# dual_encoder_i2c_revB.net
KiCad netlist of a schematic drawn in EAGLE
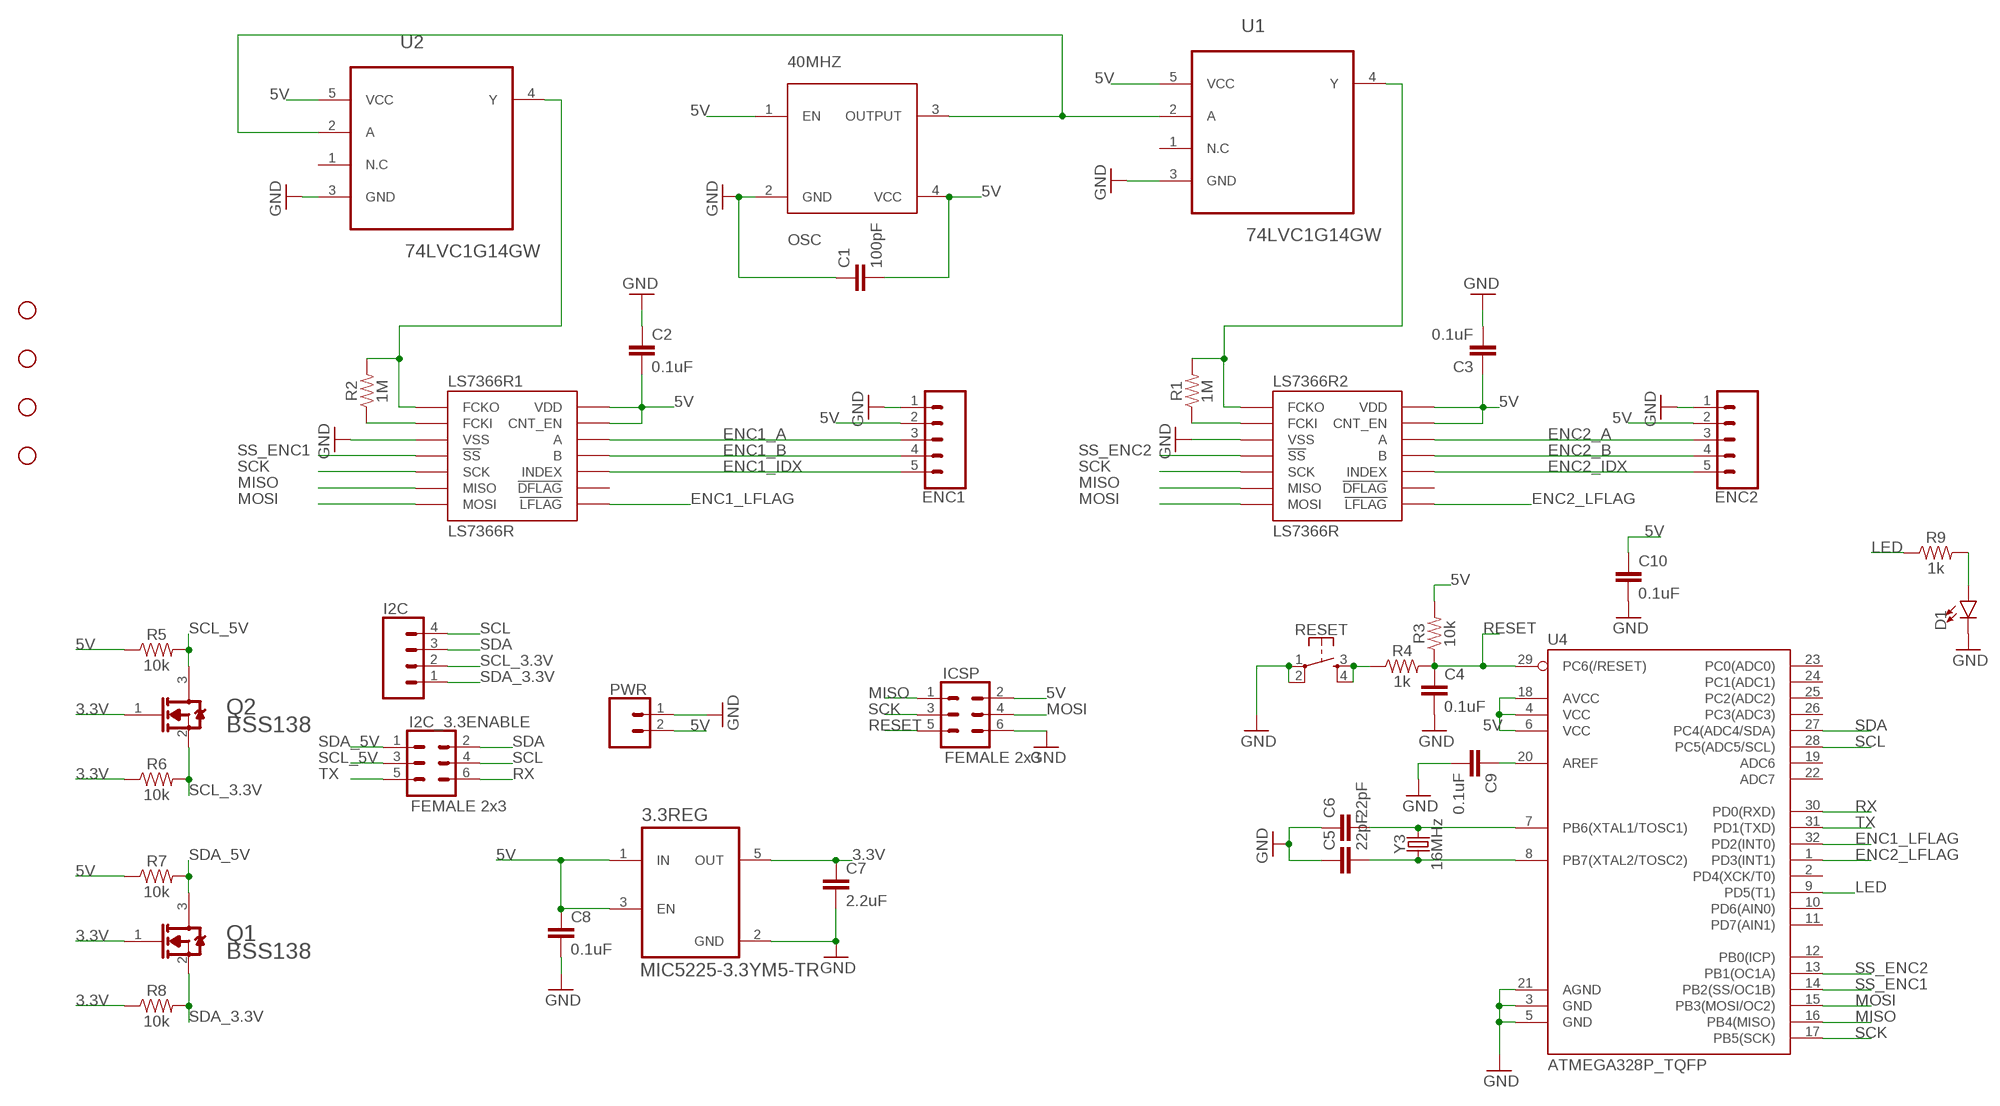
[diagram p0: schematic, sheet 1]

(export (version "E")
  (design (tool "Eeschema 10.0.6"))
  (components
    (comp (ref "3.3REG")
      (value "MIC5225-3.3YM5-TR")
      (footprint "eagle-import:SOT95P280X145-5N")
      (fields (field (name "MF") "Microchip"))
      (libsource (lib "eagle-import") (part "MIC5225-3.3YM5-TR"))
    )
    (comp (ref "40MHZ")
      (value "OSC")
      (footprint "eagle-import:CB3OSCILLATOR")
      (libsource (lib "eagle-import") (part "OSC"))
    )
    (comp (ref "C1")
      (value "100pF")
      (footprint "eagle-import:0603")
      (libsource (lib "eagle-import") (part "100PF-0603-50V-5%"))
    )
    (comp (ref "C2")
      (value "0.1uF")
      (footprint "eagle-import:0603")
      (libsource (lib "eagle-import") (part "0.1UF-0603-25V-5%"))
    )
    (comp (ref "C3")
      (value "0.1uF")
      (footprint "eagle-import:0603")
      (libsource (lib "eagle-import") (part "0.1UF-0603-25V-5%"))
    )
    (comp (ref "C4")
      (value "0.1uF")
      (footprint "eagle-import:0603")
      (libsource (lib "eagle-import") (part "0.1UF-0603-25V-5%"))
    )
    (comp (ref "C5")
      (value "22pF")
      (footprint "eagle-import:0603")
      (libsource (lib "eagle-import") (part "22PF-0603-50V-5%"))
    )
    (comp (ref "C6")
      (value "22pF")
      (footprint "eagle-import:0603")
      (libsource (lib "eagle-import") (part "22PF-0603-50V-5%"))
    )
    (comp (ref "C7")
      (value "2.2uF")
      (footprint "eagle-import:0603")
      (libsource (lib "eagle-import") (part "2.2UF-0603-10V-20%"))
    )
    (comp (ref "C8")
      (value "0.1uF")
      (footprint "eagle-import:0603")
      (libsource (lib "eagle-import") (part "0.1UF-0603-25V-5%"))
    )
    (comp (ref "C9")
      (value "0.1uF")
      (footprint "eagle-import:0603")
      (libsource (lib "eagle-import") (part "0.1UF-0603-25V-5%"))
    )
    (comp (ref "C10")
      (value "0.1uF")
      (footprint "eagle-import:0603")
      (libsource (lib "eagle-import") (part "0.1UF-0603-25V-5%"))
    )
    (comp (ref "D1")
      (value "LED0603")
      (footprint "eagle-import:LED-0603")
      (libsource (lib "eagle-import") (part "LED0603"))
    )
    (comp (ref "ENC1")
      (value "CONN_05")
      (footprint "eagle-import:1X05")
      (libsource (lib "eagle-import") (part "CONN_05"))
    )
    (comp (ref "ENC2")
      (value "CONN_05")
      (footprint "eagle-import:1X05")
      (libsource (lib "eagle-import") (part "CONN_05"))
    )
    (comp (ref "H1")
      (value "STAND-OFF")
      (footprint "eagle-import:STAND-OFF")
      (libsource (lib "eagle-import") (part "STAND-OFF"))
    )
    (comp (ref "H2")
      (value "STAND-OFF")
      (footprint "eagle-import:STAND-OFF")
      (libsource (lib "eagle-import") (part "STAND-OFF"))
    )
    (comp (ref "H3")
      (value "STAND-OFF")
      (footprint "eagle-import:STAND-OFF")
      (libsource (lib "eagle-import") (part "STAND-OFF"))
    )
    (comp (ref "H4")
      (value "STAND-OFF")
      (footprint "eagle-import:STAND-OFF")
      (libsource (lib "eagle-import") (part "STAND-OFF"))
    )
    (comp (ref "I2C")
      (value "CONN_04")
      (footprint "eagle-import:1X04")
      (libsource (lib "eagle-import") (part "CONN_04"))
    )
    (comp (ref "I2C_3.3ENABLE")
      (value "FEMALE 2x3")
      (footprint "eagle-import:2X3")
      (libsource (lib "eagle-import") (part "CONN_03X2FEMALE"))
    )
    (comp (ref "ICSP")
      (value "FEMALE 2x3")
      (footprint "eagle-import:2X3")
      (libsource (lib "eagle-import") (part "CONN_03X2FEMALE"))
    )
    (comp (ref "LS7366R1")
      (value "LS7366R")
      (footprint "eagle-import:SOIC14")
      (fields (field (name "MF") "LSI"))
      (libsource (lib "eagle-import") (part "LS7366R"))
    )
    (comp (ref "LS7366R2")
      (value "LS7366R")
      (footprint "eagle-import:SOIC14")
      (fields (field (name "MF") "LSI"))
      (libsource (lib "eagle-import") (part "LS7366R"))
    )
    (comp (ref "PWR")
      (value "CONN_02-JST-2MM-SMT")
      (footprint "eagle-import:JST-2-SMD")
      (libsource (lib "eagle-import") (part "CONN_02-JST-2MM-SMT"))
    )
    (comp (ref "Q1")
      (value "ON_SEMI_BSS138ON_SEMI_BSS138_0_0")
      (footprint "eagle-import:ON_SEMI_BSS138_0")
      (fields
        (field (name "DIGIKEY_PART_NUMBER") "BSS138CT-ND")
        (field (name "MF") "ON Semi")
        (field (name "MOUSER_PART_NUMBER") "512-BSS138")
      )
      (libsource (lib "eagle-import") (part "ON_SEMI_BSS138ON_SEMI_BSS138_0_0"))
    )
    (comp (ref "Q2")
      (value "ON_SEMI_BSS138ON_SEMI_BSS138_0_0")
      (footprint "eagle-import:ON_SEMI_BSS138_0")
      (fields
        (field (name "DIGIKEY_PART_NUMBER") "BSS138CT-ND")
        (field (name "MF") "ON Semi")
        (field (name "MOUSER_PART_NUMBER") "512-BSS138")
      )
      (libsource (lib "eagle-import") (part "ON_SEMI_BSS138ON_SEMI_BSS138_0_0"))
    )
    (comp (ref "R1")
      (value "1M")
      (footprint "eagle-import:0603")
      (libsource (lib "eagle-import") (part "1MOHM-0603-1/4W-5%"))
    )
    (comp (ref "R2")
      (value "1M")
      (footprint "eagle-import:0603")
      (libsource (lib "eagle-import") (part "1MOHM-0603-1/4W-5%"))
    )
    (comp (ref "R3")
      (value "10k")
      (footprint "eagle-import:0603")
      (libsource (lib "eagle-import") (part "10KOHM-0603-1/10W-1%"))
    )
    (comp (ref "R4")
      (value "1k")
      (footprint "eagle-import:0603")
      (libsource (lib "eagle-import") (part "1KOHM-0603-1/10W-1%"))
    )
    (comp (ref "R5")
      (value "10k")
      (footprint "eagle-import:0603")
      (libsource (lib "eagle-import") (part "10KOHM-0603-1/10W-1%"))
    )
    (comp (ref "R6")
      (value "10k")
      (footprint "eagle-import:0603")
      (libsource (lib "eagle-import") (part "10KOHM-0603-1/10W-1%"))
    )
    (comp (ref "R7")
      (value "10k")
      (footprint "eagle-import:0603")
      (libsource (lib "eagle-import") (part "10KOHM-0603-1/10W-1%"))
    )
    (comp (ref "R8")
      (value "10k")
      (footprint "eagle-import:0603")
      (libsource (lib "eagle-import") (part "10KOHM-0603-1/10W-1%"))
    )
    (comp (ref "R9")
      (value "1k")
      (footprint "eagle-import:0603")
      (libsource (lib "eagle-import") (part "1KOHM-0603-1/10W-1%"))
    )
    (comp (ref "RESET")
      (value "MOMENTARY-SWITCH-SPST-2-SMD-5.2MM")
      (footprint "eagle-import:TACTILE_SWITCH_SMD_5.2MM")
      (libsource (lib "eagle-import") (part "MOMENTARY-SWITCH-SPST-2-SMD-5.2MM"))
    )
    (comp (ref "U1")
      (value "74LVC1G14GW")
      (footprint "eagle-import:SOT65P210X110-5N")
      (fields (field (name "MF") "NXP Semiconductors"))
      (libsource (lib "eagle-import") (part "74LVC1G14GW"))
    )
    (comp (ref "U2")
      (value "74LVC1G14GW")
      (footprint "eagle-import:SOT65P210X110-5N")
      (fields (field (name "MF") "NXP Semiconductors"))
      (libsource (lib "eagle-import") (part "74LVC1G14GW"))
    )
    (comp (ref "U4")
      (value "ATMEGA328P_TQFP")
      (footprint "eagle-import:TQFP32-08")
      (libsource (lib "eagle-import") (part "ATMEGA328P_TQFP"))
    )
    (comp (ref "Y3")
      (value "16MHz")
      (footprint "eagle-import:CRYSTAL-SMD-5X3.2-4PAD")
      (libsource (lib "eagle-import") (part "CRYSTAL-16MHZSMD-5X3.2"))
    )
  )
  (nets
    (net (code "1") (name "/3.3V") (class "Default")
      (node (ref "3.3REG") (pin "5") (pinfunction "OUT_5") (pintype "output"))
      (node (ref "C7") (pin "1") (pinfunction "1_1") (pintype "passive"))
      (node (ref "Q1") (pin "1") (pinfunction "G_1") (pintype "bidirectional"))
      (node (ref "Q2") (pin "1") (pinfunction "G_1") (pintype "bidirectional"))
      (node (ref "R6") (pin "1") (pinfunction "1_1") (pintype "passive"))
      (node (ref "R8") (pin "1") (pinfunction "1_1") (pintype "passive"))
    )
    (net (code "2") (name "/5V") (class "Default")
      (node (ref "3.3REG") (pin "1") (pinfunction "IN_1") (pintype "input"))
      (node (ref "3.3REG") (pin "3") (pinfunction "EN_3") (pintype "input"))
      (node (ref "40MHZ") (pin "1") (pinfunction "EN_1") (pintype "input"))
      (node (ref "40MHZ") (pin "4") (pinfunction "VCC_4") (pintype "input"))
      (node (ref "C1") (pin "2") (pinfunction "2_2") (pintype "passive"))
      (node (ref "C10") (pin "1") (pinfunction "1_1") (pintype "passive"))
      (node (ref "C2") (pin "2") (pinfunction "2_2") (pintype "passive"))
      (node (ref "C3") (pin "1") (pinfunction "1_1") (pintype "passive"))
      (node (ref "C8") (pin "1") (pinfunction "1_1") (pintype "passive"))
      (node (ref "ENC1") (pin "2") (pinfunction "2_2") (pintype "passive"))
      (node (ref "ENC2") (pin "2") (pinfunction "2_2") (pintype "passive"))
      (node (ref "ICSP") (pin "2") (pinfunction "2_2") (pintype "bidirectional"))
      (node (ref "LS7366R1") (pin "13") (pinfunction "CNT_EN_13") (pintype "bidirectional"))
      (node (ref "LS7366R1") (pin "14") (pinfunction "VDD_14") (pintype "bidirectional"))
      (node (ref "LS7366R2") (pin "13") (pinfunction "CNT_EN_13") (pintype "bidirectional"))
      (node (ref "LS7366R2") (pin "14") (pinfunction "VDD_14") (pintype "bidirectional"))
      (node (ref "PWR") (pin "2") (pinfunction "1_2") (pintype "passive"))
      (node (ref "R3") (pin "2") (pinfunction "2_2") (pintype "passive"))
      (node (ref "R5") (pin "1") (pinfunction "1_1") (pintype "passive"))
      (node (ref "R7") (pin "1") (pinfunction "1_1") (pintype "passive"))
      (node (ref "U1") (pin "5") (pinfunction "VCC_5") (pintype "power_in"))
      (node (ref "U2") (pin "5") (pinfunction "VCC_5") (pintype "power_in"))
      (node (ref "U4") (pin "18") (pinfunction "AVCC_18") (pintype "bidirectional"))
      (node (ref "U4") (pin "4") (pinfunction "VCC_4") (pintype "bidirectional"))
      (node (ref "U4") (pin "6") (pinfunction "VCC_6") (pintype "bidirectional"))
    )
    (net (code "3") (name "/ENC1_A") (class "Default")
      (node (ref "ENC1") (pin "3") (pinfunction "3_3") (pintype "passive"))
      (node (ref "LS7366R1") (pin "12") (pinfunction "A_12") (pintype "bidirectional"))
    )
    (net (code "4") (name "/ENC1_B") (class "Default")
      (node (ref "ENC1") (pin "4") (pinfunction "4_4") (pintype "passive"))
      (node (ref "LS7366R1") (pin "11") (pinfunction "B_11") (pintype "bidirectional"))
    )
    (net (code "5") (name "/ENC1_IDX") (class "Default")
      (node (ref "ENC1") (pin "5") (pinfunction "5_5") (pintype "passive"))
      (node (ref "LS7366R1") (pin "10") (pinfunction "INDEX_10") (pintype "bidirectional"))
    )
    (net (code "6") (name "/ENC1_LFLAG") (class "Default")
      (node (ref "LS7366R1") (pin "8") (pinfunction "~{LFLAG}_8") (pintype "bidirectional"))
      (node (ref "U4") (pin "32") (pinfunction "PD2(INT0)_32") (pintype "bidirectional"))
    )
    (net (code "7") (name "/ENC2_A") (class "Default")
      (node (ref "ENC2") (pin "3") (pinfunction "3_3") (pintype "passive"))
      (node (ref "LS7366R2") (pin "12") (pinfunction "A_12") (pintype "bidirectional"))
    )
    (net (code "8") (name "/ENC2_B") (class "Default")
      (node (ref "ENC2") (pin "4") (pinfunction "4_4") (pintype "passive"))
      (node (ref "LS7366R2") (pin "11") (pinfunction "B_11") (pintype "bidirectional"))
    )
    (net (code "9") (name "/ENC2_IDX") (class "Default")
      (node (ref "ENC2") (pin "5") (pinfunction "5_5") (pintype "passive"))
      (node (ref "LS7366R2") (pin "10") (pinfunction "INDEX_10") (pintype "bidirectional"))
    )
    (net (code "10") (name "/ENC2_LFLAG") (class "Default")
      (node (ref "LS7366R2") (pin "8") (pinfunction "~{LFLAG}_8") (pintype "bidirectional"))
      (node (ref "U4") (pin "1") (pinfunction "PD3(INT1)_1") (pintype "bidirectional"))
    )
    (net (code "11") (name "/LED") (class "Default")
      (node (ref "R9") (pin "1") (pinfunction "1_1") (pintype "passive"))
      (node (ref "U4") (pin "9") (pinfunction "PD5(T1)_9") (pintype "bidirectional"))
    )
    (net (code "12") (name "/MISO") (class "Default")
      (node (ref "ICSP") (pin "1") (pinfunction "1_1") (pintype "bidirectional"))
      (node (ref "LS7366R1") (pin "6") (pinfunction "MISO_6") (pintype "bidirectional"))
      (node (ref "LS7366R2") (pin "6") (pinfunction "MISO_6") (pintype "bidirectional"))
      (node (ref "U4") (pin "16") (pinfunction "PB4(MISO)_16") (pintype "bidirectional"))
    )
    (net (code "13") (name "/MOSI") (class "Default")
      (node (ref "ICSP") (pin "4") (pinfunction "4_4") (pintype "bidirectional"))
      (node (ref "LS7366R1") (pin "7") (pinfunction "MOSI_7") (pintype "bidirectional"))
      (node (ref "LS7366R2") (pin "7") (pinfunction "MOSI_7") (pintype "bidirectional"))
      (node (ref "U4") (pin "15") (pinfunction "PB3(MOSI/OC2)_15") (pintype "bidirectional"))
    )
    (net (code "14") (name "/RESET") (class "Default")
      (node (ref "C4") (pin "1") (pinfunction "1_1") (pintype "passive"))
      (node (ref "ICSP") (pin "5") (pinfunction "5_5") (pintype "bidirectional"))
      (node (ref "R3") (pin "1") (pinfunction "1_1") (pintype "passive"))
      (node (ref "R4") (pin "2") (pinfunction "2_2") (pintype "passive"))
      (node (ref "U4") (pin "29") (pinfunction "PC6(/RESET)_29") (pintype "bidirectional"))
    )
    (net (code "15") (name "/RX") (class "Default")
      (node (ref "I2C_3.3ENABLE") (pin "6") (pinfunction "6_6") (pintype "bidirectional"))
      (node (ref "U4") (pin "30") (pinfunction "PD0(RXD)_30") (pintype "bidirectional"))
    )
    (net (code "16") (name "/SCK") (class "Default")
      (node (ref "ICSP") (pin "3") (pinfunction "3_3") (pintype "bidirectional"))
      (node (ref "LS7366R1") (pin "5") (pinfunction "SCK_5") (pintype "bidirectional"))
      (node (ref "LS7366R2") (pin "5") (pinfunction "SCK_5") (pintype "bidirectional"))
      (node (ref "U4") (pin "17") (pinfunction "PB5(SCK)_17") (pintype "bidirectional"))
    )
    (net (code "17") (name "/SCL") (class "Default")
      (node (ref "I2C") (pin "4") (pinfunction "4_4") (pintype "passive"))
      (node (ref "I2C_3.3ENABLE") (pin "4") (pinfunction "4_4") (pintype "bidirectional"))
      (node (ref "U4") (pin "28") (pinfunction "PC5(ADC5/SCL)_28") (pintype "bidirectional"))
    )
    (net (code "18") (name "/SCL_3.3V") (class "Default")
      (node (ref "I2C") (pin "2") (pinfunction "2_2") (pintype "passive"))
      (node (ref "Q2") (pin "2") (pinfunction "S_2") (pintype "bidirectional"))
      (node (ref "R6") (pin "2") (pinfunction "2_2") (pintype "passive"))
    )
    (net (code "19") (name "/SCL_5V") (class "Default")
      (node (ref "I2C_3.3ENABLE") (pin "3") (pinfunction "3_3") (pintype "bidirectional"))
      (node (ref "Q2") (pin "3") (pinfunction "D_3") (pintype "bidirectional"))
      (node (ref "R5") (pin "2") (pinfunction "2_2") (pintype "passive"))
    )
    (net (code "20") (name "/SDA") (class "Default")
      (node (ref "I2C") (pin "3") (pinfunction "3_3") (pintype "passive"))
      (node (ref "I2C_3.3ENABLE") (pin "2") (pinfunction "2_2") (pintype "bidirectional"))
      (node (ref "U4") (pin "27") (pinfunction "PC4(ADC4/SDA)_27") (pintype "bidirectional"))
    )
    (net (code "21") (name "/SDA_3.3V") (class "Default")
      (node (ref "I2C") (pin "1") (pinfunction "1_1") (pintype "passive"))
      (node (ref "Q1") (pin "2") (pinfunction "S_2") (pintype "bidirectional"))
      (node (ref "R8") (pin "2") (pinfunction "2_2") (pintype "passive"))
    )
    (net (code "22") (name "/SDA_5V") (class "Default")
      (node (ref "I2C_3.3ENABLE") (pin "1") (pinfunction "1_1") (pintype "bidirectional"))
      (node (ref "Q1") (pin "3") (pinfunction "D_3") (pintype "bidirectional"))
      (node (ref "R7") (pin "2") (pinfunction "2_2") (pintype "passive"))
    )
    (net (code "23") (name "/SS_ENC1") (class "Default")
      (node (ref "LS7366R1") (pin "4") (pinfunction "~{SS}_4") (pintype "bidirectional"))
      (node (ref "U4") (pin "14") (pinfunction "PB2(SS/OC1B)_14") (pintype "bidirectional"))
    )
    (net (code "24") (name "/SS_ENC2") (class "Default")
      (node (ref "LS7366R2") (pin "4") (pinfunction "~{SS}_4") (pintype "bidirectional"))
      (node (ref "U4") (pin "13") (pinfunction "PB1(OC1A)_13") (pintype "bidirectional"))
    )
    (net (code "25") (name "/TX") (class "Default")
      (node (ref "I2C_3.3ENABLE") (pin "5") (pinfunction "5_5") (pintype "bidirectional"))
      (node (ref "U4") (pin "31") (pinfunction "PD1(TXD)_31") (pintype "bidirectional"))
    )
    (net (code "26") (name "GND") (class "Default")
      (node (ref "3.3REG") (pin "2") (pinfunction "GND_2") (pintype "power_in"))
      (node (ref "40MHZ") (pin "2") (pinfunction "GND_2") (pintype "input"))
      (node (ref "C1") (pin "1") (pinfunction "1_1") (pintype "passive"))
      (node (ref "C10") (pin "2") (pinfunction "2_2") (pintype "passive"))
      (node (ref "C2") (pin "1") (pinfunction "1_1") (pintype "passive"))
      (node (ref "C3") (pin "2") (pinfunction "2_2") (pintype "passive"))
      (node (ref "C4") (pin "2") (pinfunction "2_2") (pintype "passive"))
      (node (ref "C5") (pin "1") (pinfunction "1_1") (pintype "passive"))
      (node (ref "C6") (pin "1") (pinfunction "1_1") (pintype "passive"))
      (node (ref "C7") (pin "2") (pinfunction "2_2") (pintype "passive"))
      (node (ref "C8") (pin "2") (pinfunction "2_2") (pintype "passive"))
      (node (ref "C9") (pin "2") (pinfunction "2_2") (pintype "passive"))
      (node (ref "D1") (pin "C") (pinfunction "C_C") (pintype "passive"))
      (node (ref "ENC1") (pin "1") (pinfunction "1_1") (pintype "passive"))
      (node (ref "ENC2") (pin "1") (pinfunction "1_1") (pintype "passive"))
      (node (ref "ICSP") (pin "6") (pinfunction "6_6") (pintype "bidirectional"))
      (node (ref "LS7366R1") (pin "3") (pinfunction "VSS_3") (pintype "bidirectional"))
      (node (ref "LS7366R2") (pin "3") (pinfunction "VSS_3") (pintype "bidirectional"))
      (node (ref "PWR") (pin "1") (pinfunction "2_1") (pintype "passive"))
      (node (ref "RESET") (pin "1") (pinfunction "1_1") (pintype "passive"))
      (node (ref "RESET") (pin "2") (pinfunction "2_2") (pintype "passive"))
      (node (ref "U1") (pin "3") (pinfunction "GND_3") (pintype "passive"))
      (node (ref "U2") (pin "3") (pinfunction "GND_3") (pintype "passive"))
      (node (ref "U4") (pin "21") (pinfunction "AGND_21") (pintype "bidirectional"))
      (node (ref "U4") (pin "3") (pinfunction "GND_3") (pintype "bidirectional"))
      (node (ref "U4") (pin "5") (pinfunction "GND_5") (pintype "bidirectional"))
    )
    (net (code "27") (name "Net-(40MHZ-OUTPUT)") (class "Default")
      (node (ref "40MHZ") (pin "3") (pinfunction "OUTPUT_3") (pintype "output"))
      (node (ref "U1") (pin "2") (pinfunction "A_2") (pintype "input"))
      (node (ref "U2") (pin "2") (pinfunction "A_2") (pintype "input"))
    )
    (net (code "28") (name "Net-(D1-PadA)") (class "Default")
      (node (ref "D1") (pin "A") (pinfunction "A_A") (pintype "passive"))
      (node (ref "R9") (pin "2") (pinfunction "2_2") (pintype "passive"))
    )
    (net (code "29") (name "Net-(LS7366R1-FCKI)") (class "Default")
      (node (ref "LS7366R1") (pin "2") (pinfunction "FCKI_2") (pintype "bidirectional"))
      (node (ref "R2") (pin "1") (pinfunction "1_1") (pintype "passive"))
    )
    (net (code "30") (name "Net-(LS7366R1-FCKO)") (class "Default")
      (node (ref "LS7366R1") (pin "1") (pinfunction "FCKO_1") (pintype "bidirectional"))
      (node (ref "R2") (pin "2") (pinfunction "2_2") (pintype "passive"))
      (node (ref "U2") (pin "4") (pinfunction "Y_4") (pintype "output"))
    )
    (net (code "31") (name "Net-(LS7366R2-FCKI)") (class "Default")
      (node (ref "LS7366R2") (pin "2") (pinfunction "FCKI_2") (pintype "bidirectional"))
      (node (ref "R1") (pin "1") (pinfunction "1_1") (pintype "passive"))
    )
    (net (code "32") (name "Net-(LS7366R2-FCKO)") (class "Default")
      (node (ref "LS7366R2") (pin "1") (pinfunction "FCKO_1") (pintype "bidirectional"))
      (node (ref "R1") (pin "2") (pinfunction "2_2") (pintype "passive"))
      (node (ref "U1") (pin "4") (pinfunction "Y_4") (pintype "output"))
    )
    (net (code "33") (name "Net-(R4-Pad1)") (class "Default")
      (node (ref "R4") (pin "1") (pinfunction "1_1") (pintype "passive"))
      (node (ref "RESET") (pin "3") (pinfunction "3_3") (pintype "passive"))
      (node (ref "RESET") (pin "4") (pinfunction "4_4") (pintype "passive"))
    )
    (net (code "34") (name "Net-(U4-AREF)") (class "Default")
      (node (ref "C9") (pin "1") (pinfunction "1_1") (pintype "passive"))
      (node (ref "U4") (pin "20") (pinfunction "AREF_20") (pintype "bidirectional"))
    )
    (net (code "35") (name "Net-(U4-PB6(XTAL1{slash}TOSC1))") (class "Default")
      (node (ref "C6") (pin "2") (pinfunction "2_2") (pintype "passive"))
      (node (ref "U4") (pin "7") (pinfunction "PB6(XTAL1/TOSC1)_7") (pintype "bidirectional"))
      (node (ref "Y3") (pin "3") (pinfunction "2_3") (pintype "passive"))
    )
    (net (code "36") (name "Net-(U4-PB7(XTAL2{slash}TOSC2))") (class "Default")
      (node (ref "C5") (pin "2") (pinfunction "2_2") (pintype "passive"))
      (node (ref "U4") (pin "8") (pinfunction "PB7(XTAL2/TOSC2)_8") (pintype "bidirectional"))
      (node (ref "Y3") (pin "1") (pinfunction "1_1") (pintype "passive"))
    )
    (net (code "37") (name "unconnected-(LS7366R1-~{DFLAG}-Pad9)") (class "Default")
      (node (ref "LS7366R1") (pin "9") (pinfunction "~{DFLAG}_9") (pintype "bidirectional"))
    )
    (net (code "38") (name "unconnected-(LS7366R2-~{DFLAG}-Pad9)") (class "Default")
      (node (ref "LS7366R2") (pin "9") (pinfunction "~{DFLAG}_9") (pintype "bidirectional"))
    )
    (net (code "39") (name "unconnected-(U1-N.C-Pad1)") (class "Default")
      (node (ref "U1") (pin "1") (pinfunction "N.C_1") (pintype "no_connect"))
    )
    (net (code "40") (name "unconnected-(U2-N.C-Pad1)") (class "Default")
      (node (ref "U2") (pin "1") (pinfunction "N.C_1") (pintype "no_connect"))
    )
    (net (code "41") (name "unconnected-(U4-ADC6-Pad19)") (class "Default")
      (node (ref "U4") (pin "19") (pinfunction "ADC6_19") (pintype "bidirectional"))
    )
    (net (code "42") (name "unconnected-(U4-ADC7-Pad22)") (class "Default")
      (node (ref "U4") (pin "22") (pinfunction "ADC7_22") (pintype "bidirectional"))
    )
    (net (code "43") (name "unconnected-(U4-PB0(ICP)-Pad12)") (class "Default")
      (node (ref "U4") (pin "12") (pinfunction "PB0(ICP)_12") (pintype "bidirectional"))
    )
    (net (code "44") (name "unconnected-(U4-PC0(ADC0)-Pad23)") (class "Default")
      (node (ref "U4") (pin "23") (pinfunction "PC0(ADC0)_23") (pintype "bidirectional"))
    )
    (net (code "45") (name "unconnected-(U4-PC1(ADC1)-Pad24)") (class "Default")
      (node (ref "U4") (pin "24") (pinfunction "PC1(ADC1)_24") (pintype "bidirectional"))
    )
    (net (code "46") (name "unconnected-(U4-PC2(ADC2)-Pad25)") (class "Default")
      (node (ref "U4") (pin "25") (pinfunction "PC2(ADC2)_25") (pintype "bidirectional"))
    )
    (net (code "47") (name "unconnected-(U4-PC3(ADC3)-Pad26)") (class "Default")
      (node (ref "U4") (pin "26") (pinfunction "PC3(ADC3)_26") (pintype "bidirectional"))
    )
    (net (code "48") (name "unconnected-(U4-PD4(XCK{slash}T0)-Pad2)") (class "Default")
      (node (ref "U4") (pin "2") (pinfunction "PD4(XCK/T0)_2") (pintype "bidirectional"))
    )
    (net (code "49") (name "unconnected-(U4-PD6(AIN0)-Pad10)") (class "Default")
      (node (ref "U4") (pin "10") (pinfunction "PD6(AIN0)_10") (pintype "bidirectional"))
    )
    (net (code "50") (name "unconnected-(U4-PD7(AIN1)-Pad11)") (class "Default")
      (node (ref "U4") (pin "11") (pinfunction "PD7(AIN1)_11") (pintype "bidirectional"))
    )
  )
)
